# SmartRock_EC.net
KiCad netlist of a schematic drawn in EAGLE
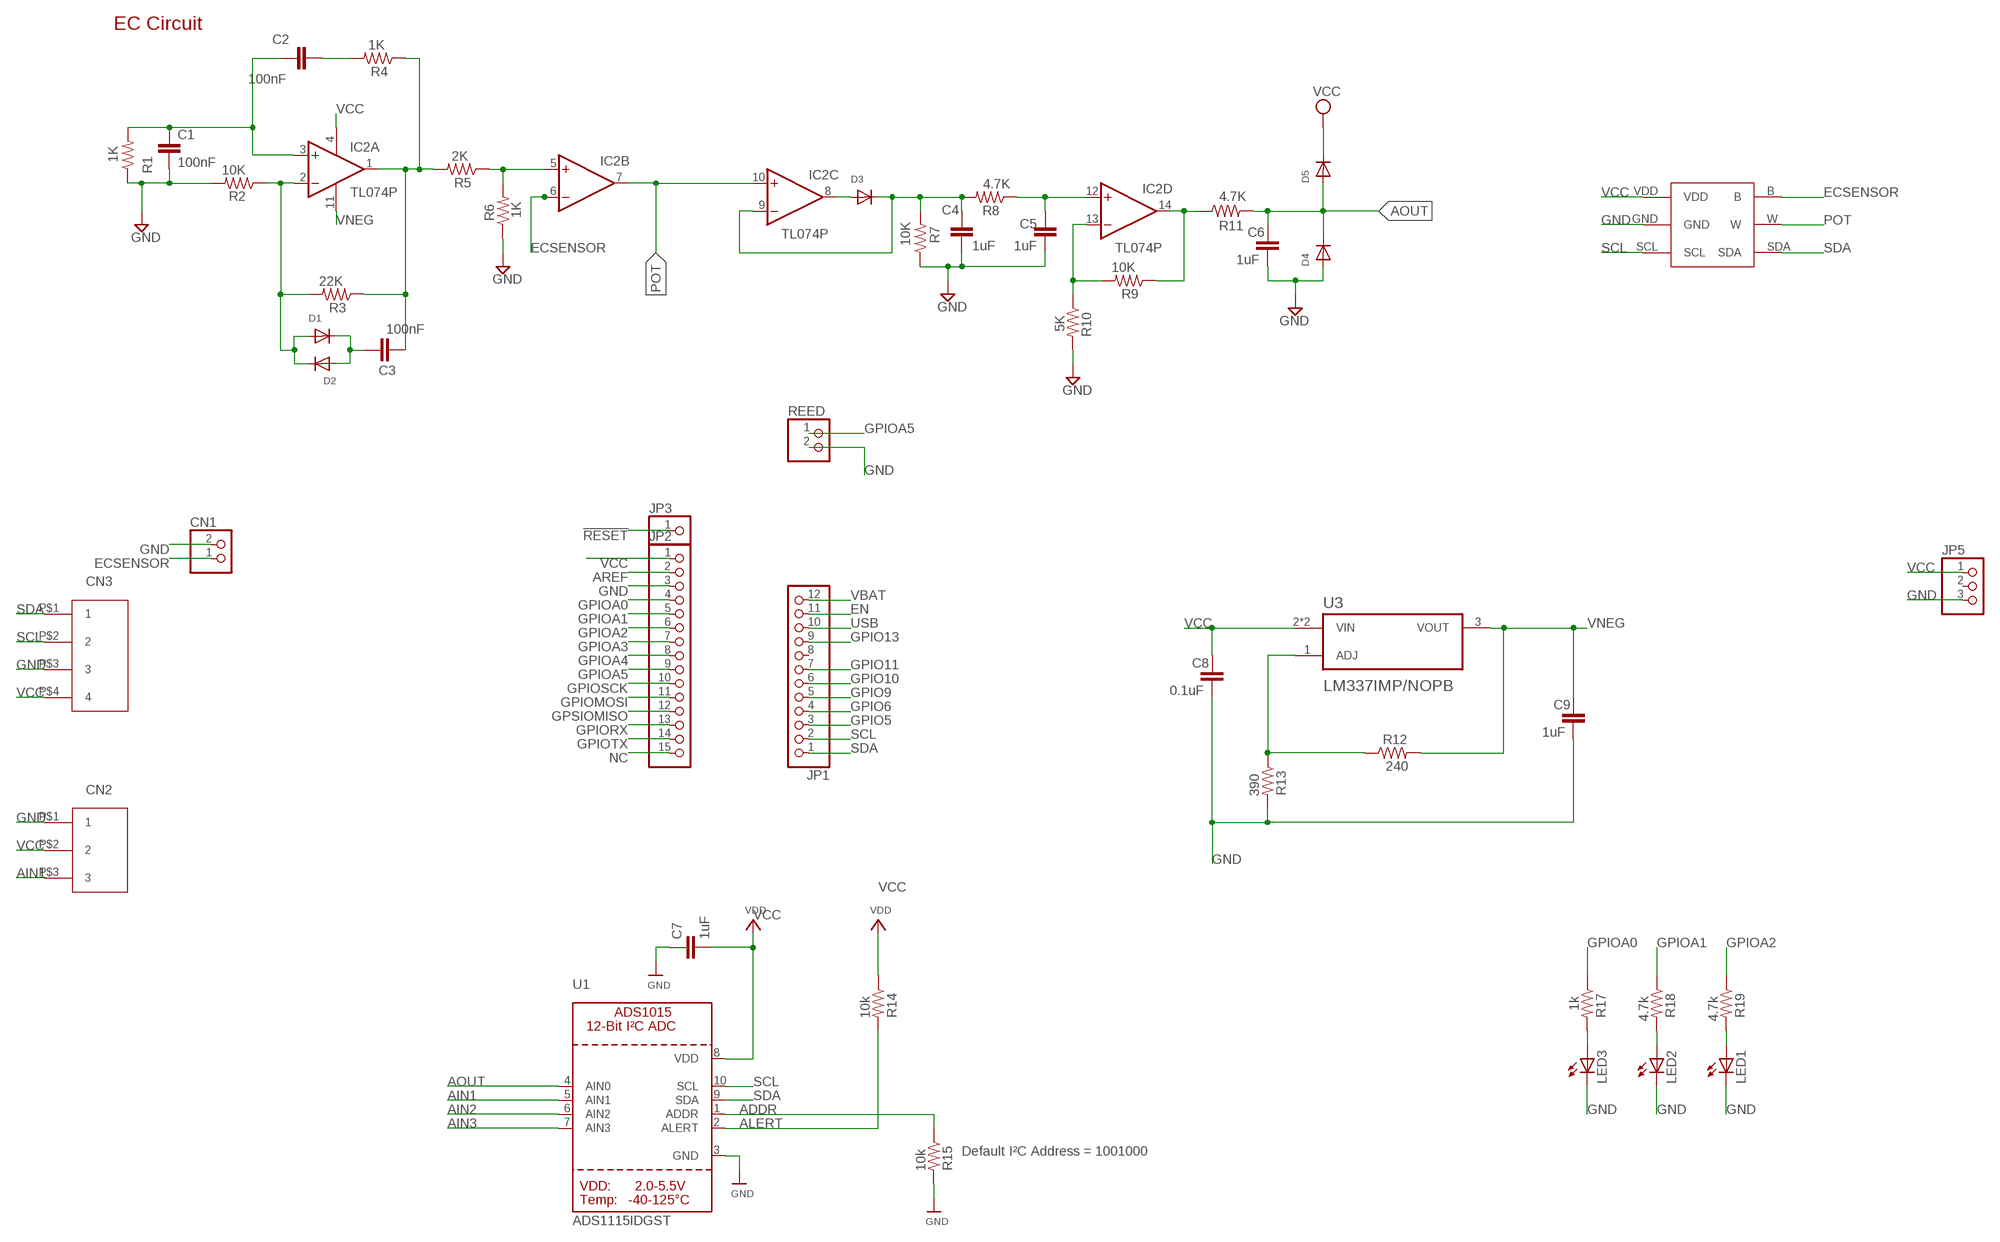
[diagram p0: schematic, sheet 1]

(export (version "E")
  (design (tool "Eeschema 10.0.6"))
  (components
    (comp (ref "C1")
      (value "100nF")
      (footprint "eagle-import:C1206")
      (libsource (lib "eagle-import") (part "C-EUC1206"))
    )
    (comp (ref "C2")
      (value "100nF")
      (footprint "eagle-import:C1206")
      (libsource (lib "eagle-import") (part "C-EUC1206"))
    )
    (comp (ref "C3")
      (value "100nF")
      (footprint "eagle-import:C1206")
      (libsource (lib "eagle-import") (part "C-EUC1206"))
    )
    (comp (ref "C4")
      (value "1uF")
      (footprint "eagle-import:C1206")
      (libsource (lib "eagle-import") (part "C-EUC1206"))
    )
    (comp (ref "C5")
      (value "1uF")
      (footprint "eagle-import:C1206")
      (libsource (lib "eagle-import") (part "C-EUC1206"))
    )
    (comp (ref "C6")
      (value "1uF")
      (footprint "eagle-import:C1206")
      (libsource (lib "eagle-import") (part "C-EUC1206"))
    )
    (comp (ref "C7")
      (value "1uF")
      (footprint "eagle-import:C1206")
      (libsource (lib "eagle-import") (part "C-EUC1206"))
    )
    (comp (ref "C8")
      (value "0.1uF")
      (footprint "eagle-import:C1206")
      (libsource (lib "eagle-import") (part "C-EUC1206"))
    )
    (comp (ref "C9")
      (value "1uF")
      (footprint "eagle-import:C1206")
      (libsource (lib "eagle-import") (part "C-EUC1206"))
    )
    (comp (ref "CN1")
      (value "JST_2PIN-THM")
      (footprint "eagle-import:JST-PH-2-THM")
      (libsource (lib "eagle-import") (part "JST_2PIN-THM"))
    )
    (comp (ref "D1")
      (value "DIODEDO-1N4148")
      (footprint "eagle-import:DO-1N4148")
      (libsource (lib "eagle-import") (part "DIODEDO-1N4148"))
    )
    (comp (ref "D2")
      (value "DIODEDO-1N4148")
      (footprint "eagle-import:DO-1N4148")
      (libsource (lib "eagle-import") (part "DIODEDO-1N4148"))
    )
    (comp (ref "D3")
      (value "DIODEDO-1N4148")
      (footprint "eagle-import:DO-1N4148")
      (libsource (lib "eagle-import") (part "DIODEDO-1N4148"))
    )
    (comp (ref "D4")
      (value "DIODEDO-1N4148")
      (footprint "eagle-import:DO-1N4148")
      (libsource (lib "eagle-import") (part "DIODEDO-1N4148"))
    )
    (comp (ref "D5")
      (value "DIODEDO-1N4148")
      (footprint "eagle-import:DO-1N4148")
      (libsource (lib "eagle-import") (part "DIODEDO-1N4148"))
    )
    (comp (ref "IC2")
      (value "TL074P")
      (footprint "eagle-import:DIL14")
      (libsource (lib "eagle-import") (part "TL074P"))
    )
    (comp (ref "JP1")
      (value "PINHD-1X12-CB")
      (footprint "eagle-import:1X12-CB")
      (libsource (lib "eagle-import") (part "PINHD-1X12-CB"))
    )
    (comp (ref "JP2")
      (value "PINHD-1X15-CB")
      (footprint "eagle-import:1X15-CB")
      (libsource (lib "eagle-import") (part "PINHD-1X15-CB"))
    )
    (comp (ref "JP3")
      (value "PINHD-1X1CB")
      (footprint "eagle-import:1X01-CLEANBIG")
      (libsource (lib "eagle-import") (part "PINHD-1X1CB"))
    )
    (comp (ref "JP5")
      (value "PINHD-1X3CB")
      (footprint "eagle-import:1X03-CLEANBIG")
      (libsource (lib "eagle-import") (part "PINHD-1X3CB"))
    )
    (comp (ref "LED1")
      (value "LEDSMT1206")
      (footprint "eagle-import:1206")
      (libsource (lib "eagle-import") (part "LEDSMT1206"))
    )
    (comp (ref "LED2")
      (value "LEDSMT1206")
      (footprint "eagle-import:1206")
      (libsource (lib "eagle-import") (part "LEDSMT1206"))
    )
    (comp (ref "LED3")
      (value "LEDSMT1206")
      (footprint "eagle-import:1206")
      (libsource (lib "eagle-import") (part "LEDSMT1206"))
    )
    (comp (ref "R1")
      (value "1K")
      (footprint "eagle-import:R1206")
      (libsource (lib "eagle-import") (part "R-US_R1206"))
    )
    (comp (ref "R2")
      (value "10K")
      (footprint "eagle-import:R1206")
      (libsource (lib "eagle-import") (part "R-US_R1206"))
    )
    (comp (ref "R3")
      (value "22K")
      (footprint "eagle-import:R1206")
      (libsource (lib "eagle-import") (part "R-US_R1206"))
    )
    (comp (ref "R4")
      (value "1K")
      (footprint "eagle-import:R1206")
      (libsource (lib "eagle-import") (part "R-US_R1206"))
    )
    (comp (ref "R5")
      (value "2K")
      (footprint "eagle-import:R1206")
      (libsource (lib "eagle-import") (part "R-US_R1206"))
    )
    (comp (ref "R6")
      (value "1K")
      (footprint "eagle-import:R1206")
      (libsource (lib "eagle-import") (part "R-US_R1206"))
    )
    (comp (ref "R7")
      (value "10K")
      (footprint "eagle-import:R1206")
      (libsource (lib "eagle-import") (part "R-US_R1206"))
    )
    (comp (ref "R8")
      (value "4.7K")
      (footprint "eagle-import:R1206")
      (libsource (lib "eagle-import") (part "R-US_R1206"))
    )
    (comp (ref "R9")
      (value "10K")
      (footprint "eagle-import:R1206")
      (libsource (lib "eagle-import") (part "R-US_R1206"))
    )
    (comp (ref "R10")
      (value "5K")
      (footprint "eagle-import:R1206")
      (libsource (lib "eagle-import") (part "R-US_R1206"))
    )
    (comp (ref "R11")
      (value "4.7K")
      (footprint "eagle-import:R1206")
      (libsource (lib "eagle-import") (part "R-US_R1206"))
    )
    (comp (ref "R12")
      (value "240")
      (footprint "eagle-import:R1206")
      (libsource (lib "eagle-import") (part "R-US_R1206"))
    )
    (comp (ref "R13")
      (value "390")
      (footprint "eagle-import:R1206")
      (libsource (lib "eagle-import") (part "R-US_R1206"))
    )
    (comp (ref "R14")
      (value "10k")
      (footprint "eagle-import:R1206")
      (libsource (lib "eagle-import") (part "R-US_R1206"))
    )
    (comp (ref "R15")
      (value "10k")
      (footprint "eagle-import:R1206")
      (libsource (lib "eagle-import") (part "R-US_R1206"))
    )
    (comp (ref "R17")
      (value "1k")
      (footprint "eagle-import:R1206")
      (libsource (lib "eagle-import") (part "R-US_R1206"))
    )
    (comp (ref "R18")
      (value "4.7k")
      (footprint "eagle-import:R1206")
      (libsource (lib "eagle-import") (part "R-US_R1206"))
    )
    (comp (ref "R19")
      (value "4.7k")
      (footprint "eagle-import:R1206")
      (libsource (lib "eagle-import") (part "R-US_R1206"))
    )
    (comp (ref "REED")
      (value "PINHD-1X2")
      (footprint "eagle-import:1X02")
      (libsource (lib "eagle-import") (part "PINHD-1X2"))
    )
    (comp (ref "U$1")
      (value "AD5246")
      (footprint "eagle-import:AD5246")
      (libsource (lib "eagle-import") (part "AD5246"))
    )
    (comp (ref "U$7")
      (value "JST_4PIN_2MM")
      (footprint "eagle-import:JST_4PIN_2MM")
      (libsource (lib "eagle-import") (part "JST_4PIN_2MM"))
    )
    (comp (ref "U$9")
      (value "JST_3PIN_2MM")
      (footprint "eagle-import:JST_3PIN_2MM")
      (libsource (lib "eagle-import") (part "JST_3PIN_2MM"))
    )
    (comp (ref "U1")
      (value "ADS1115IDGST")
      (footprint "eagle-import:MSOP10")
      (libsource (lib "eagle-import") (part "ADC_ADS1015"))
    )
    (comp (ref "U3")
      (value "LM337IMP/NOPB")
      (footprint "eagle-import:SOT230P700X180-4N")
      (fields
        (field (name "DIGI-KEY_PART_NUMBER") "LM337IMPCT-ND")
        (field (name "MF") "Texas Instruments")
        (field (name "MP") "LM337IMP")
      )
      (libsource (lib "eagle-import") (part "LM337IMP/NOPB"))
    )
  )
  (nets
    (net (code "1") (name "/ADDR") (class "Default")
      (node (ref "R15") (pin "1") (pinfunction "1_1") (pintype "passive"))
      (node (ref "U1") (pin "1") (pinfunction "ADDR_1") (pintype "bidirectional"))
    )
    (net (code "2") (name "/AIN1") (class "Default")
      (node (ref "U$9") (pin "P$3") (pinfunction "3_P$3") (pintype "bidirectional"))
      (node (ref "U1") (pin "5") (pinfunction "AIN1_5") (pintype "bidirectional"))
    )
    (net (code "3") (name "/AIN2") (class "Default")
      (node (ref "U1") (pin "6") (pinfunction "AIN2_6") (pintype "bidirectional"))
    )
    (net (code "4") (name "/AIN3") (class "Default")
      (node (ref "U1") (pin "7") (pinfunction "AIN3_7") (pintype "bidirectional"))
    )
    (net (code "5") (name "/ALERT") (class "Default")
      (node (ref "R14") (pin "2") (pinfunction "2_2") (pintype "passive"))
      (node (ref "U1") (pin "2") (pinfunction "ALERT_2") (pintype "bidirectional"))
    )
    (net (code "6") (name "/AREF") (class "Default")
      (node (ref "JP2") (pin "2") (pinfunction "2_2") (pintype "passive"))
    )
    (net (code "7") (name "/ECSENSOR") (class "Default")
      (node (ref "CN1") (pin "1") (pinfunction "2_1") (pintype "passive"))
      (node (ref "IC2") (pin "6") (pinfunction "-IN_6") (pintype "input"))
      (node (ref "U$1") (pin "B") (pinfunction "B_B") (pintype "bidirectional"))
    )
    (net (code "8") (name "/EN") (class "Default")
      (node (ref "JP1") (pin "11") (pinfunction "11_11") (pintype "passive"))
    )
    (net (code "9") (name "/GPIO5") (class "Default")
      (node (ref "JP1") (pin "3") (pinfunction "3_3") (pintype "passive"))
    )
    (net (code "10") (name "/GPIO6") (class "Default")
      (node (ref "JP1") (pin "4") (pinfunction "4_4") (pintype "passive"))
    )
    (net (code "11") (name "/GPIO9") (class "Default")
      (node (ref "JP1") (pin "5") (pinfunction "5_5") (pintype "passive"))
    )
    (net (code "12") (name "/GPIO10") (class "Default")
      (node (ref "JP1") (pin "6") (pinfunction "6_6") (pintype "passive"))
    )
    (net (code "13") (name "/GPIO11") (class "Default")
      (node (ref "JP1") (pin "7") (pinfunction "7_7") (pintype "passive"))
    )
    (net (code "14") (name "/GPIO13") (class "Default")
      (node (ref "JP1") (pin "9") (pinfunction "9_9") (pintype "passive"))
    )
    (net (code "15") (name "/GPIOA0") (class "Default")
      (node (ref "JP2") (pin "4") (pinfunction "4_4") (pintype "passive"))
      (node (ref "R17") (pin "1") (pinfunction "1_1") (pintype "passive"))
    )
    (net (code "16") (name "/GPIOA1") (class "Default")
      (node (ref "JP2") (pin "5") (pinfunction "5_5") (pintype "passive"))
      (node (ref "R18") (pin "1") (pinfunction "1_1") (pintype "passive"))
    )
    (net (code "17") (name "/GPIOA2") (class "Default")
      (node (ref "JP2") (pin "6") (pinfunction "6_6") (pintype "passive"))
      (node (ref "R19") (pin "1") (pinfunction "1_1") (pintype "passive"))
    )
    (net (code "18") (name "/GPIOA3") (class "Default")
      (node (ref "JP2") (pin "7") (pinfunction "7_7") (pintype "passive"))
    )
    (net (code "19") (name "/GPIOA4") (class "Default")
      (node (ref "JP2") (pin "8") (pinfunction "8_8") (pintype "passive"))
    )
    (net (code "20") (name "/GPIOA5") (class "Default")
      (node (ref "JP2") (pin "9") (pinfunction "9_9") (pintype "passive"))
      (node (ref "REED") (pin "1") (pinfunction "1_1") (pintype "passive"))
    )
    (net (code "21") (name "/GPIOMOSI") (class "Default")
      (node (ref "JP2") (pin "11") (pinfunction "11_11") (pintype "passive"))
    )
    (net (code "22") (name "/GPIORX") (class "Default")
      (node (ref "JP2") (pin "13") (pinfunction "13_13") (pintype "passive"))
    )
    (net (code "23") (name "/GPIOSCK") (class "Default")
      (node (ref "JP2") (pin "10") (pinfunction "10_10") (pintype "passive"))
    )
    (net (code "24") (name "/GPIOTX") (class "Default")
      (node (ref "JP2") (pin "14") (pinfunction "14_14") (pintype "passive"))
    )
    (net (code "25") (name "/GPSIOMISO") (class "Default")
      (node (ref "JP2") (pin "12") (pinfunction "12_12") (pintype "passive"))
    )
    (net (code "26") (name "/NC") (class "Default")
      (node (ref "JP2") (pin "15") (pinfunction "15_15") (pintype "passive"))
    )
    (net (code "27") (name "/SCL") (class "Default")
      (node (ref "JP1") (pin "2") (pinfunction "2_2") (pintype "passive"))
      (node (ref "U$1") (pin "SCL") (pinfunction "SCL_SCL") (pintype "bidirectional"))
      (node (ref "U$7") (pin "P$2") (pinfunction "2_P$2") (pintype "bidirectional"))
      (node (ref "U1") (pin "10") (pinfunction "SCL_10") (pintype "bidirectional"))
    )
    (net (code "28") (name "/SDA") (class "Default")
      (node (ref "JP1") (pin "1") (pinfunction "1_1") (pintype "passive"))
      (node (ref "U$1") (pin "SDA") (pinfunction "SDA_SDA") (pintype "bidirectional"))
      (node (ref "U$7") (pin "P$1") (pinfunction "1_P$1") (pintype "bidirectional"))
      (node (ref "U1") (pin "9") (pinfunction "SDA_9") (pintype "bidirectional"))
    )
    (net (code "29") (name "/USB") (class "Default")
      (node (ref "JP1") (pin "10") (pinfunction "10_10") (pintype "passive"))
    )
    (net (code "30") (name "/VBAT") (class "Default")
      (node (ref "JP1") (pin "12") (pinfunction "12_12") (pintype "passive"))
    )
    (net (code "31") (name "/VNEG") (class "Default")
      (node (ref "C9") (pin "2") (pinfunction "2_2") (pintype "passive"))
      (node (ref "IC2") (pin "11") (pinfunction "V-_11") (pintype "power_in"))
      (node (ref "R12") (pin "2") (pinfunction "2_2") (pintype "passive"))
      (node (ref "U3") (pin "3") (pinfunction "VOUT_3") (pintype "output"))
    )
    (net (code "32") (name "/~{RESET}") (class "Default")
      (node (ref "JP3") (pin "1") (pinfunction "1_1") (pintype "passive"))
    )
    (net (code "33") (name "AOUT") (class "Default")
      (node (ref "C6") (pin "2") (pinfunction "2_2") (pintype "passive"))
      (node (ref "D4") (pin "C") (pinfunction "C_C") (pintype "passive"))
      (node (ref "D5") (pin "A") (pinfunction "A_A") (pintype "passive"))
      (node (ref "R11") (pin "2") (pinfunction "2_2") (pintype "passive"))
      (node (ref "U1") (pin "4") (pinfunction "AIN0_4") (pintype "bidirectional"))
    )
    (net (code "34") (name "GND") (class "Default")
      (node (ref "C1") (pin "2") (pinfunction "2_2") (pintype "passive"))
      (node (ref "C4") (pin "1") (pinfunction "1_1") (pintype "passive"))
      (node (ref "C5") (pin "1") (pinfunction "1_1") (pintype "passive"))
      (node (ref "C6") (pin "1") (pinfunction "1_1") (pintype "passive"))
      (node (ref "C7") (pin "1") (pinfunction "1_1") (pintype "passive"))
      (node (ref "C8") (pin "1") (pinfunction "1_1") (pintype "passive"))
      (node (ref "C9") (pin "1") (pinfunction "1_1") (pintype "passive"))
      (node (ref "CN1") (pin "2") (pinfunction "1_2") (pintype "passive"))
      (node (ref "D4") (pin "A") (pinfunction "A_A") (pintype "passive"))
      (node (ref "JP2") (pin "3") (pinfunction "3_3") (pintype "passive"))
      (node (ref "JP5") (pin "3") (pinfunction "3_3") (pintype "passive"))
      (node (ref "LED1") (pin "C") (pinfunction "C_C") (pintype "passive"))
      (node (ref "LED2") (pin "C") (pinfunction "C_C") (pintype "passive"))
      (node (ref "LED3") (pin "C") (pinfunction "C_C") (pintype "passive"))
      (node (ref "R1") (pin "1") (pinfunction "1_1") (pintype "passive"))
      (node (ref "R10") (pin "2") (pinfunction "2_2") (pintype "passive"))
      (node (ref "R13") (pin "2") (pinfunction "2_2") (pintype "passive"))
      (node (ref "R15") (pin "2") (pinfunction "2_2") (pintype "passive"))
      (node (ref "R2") (pin "2") (pinfunction "2_2") (pintype "passive"))
      (node (ref "R6") (pin "1") (pinfunction "1_1") (pintype "passive"))
      (node (ref "R7") (pin "1") (pinfunction "1_1") (pintype "passive"))
      (node (ref "REED") (pin "2") (pinfunction "2_2") (pintype "passive"))
      (node (ref "U$1") (pin "GND") (pinfunction "GND_GND") (pintype "bidirectional"))
      (node (ref "U$7") (pin "P$3") (pinfunction "3_P$3") (pintype "bidirectional"))
      (node (ref "U$9") (pin "P$1") (pinfunction "1_P$1") (pintype "bidirectional"))
      (node (ref "U1") (pin "3") (pinfunction "GND_3") (pintype "bidirectional"))
    )
    (net (code "35") (name "Net-(C2-Pad2)") (class "Default")
      (node (ref "C2") (pin "2") (pinfunction "2_2") (pintype "passive"))
      (node (ref "R4") (pin "2") (pinfunction "2_2") (pintype "passive"))
    )
    (net (code "36") (name "Net-(C3-Pad1)") (class "Default")
      (node (ref "C3") (pin "1") (pinfunction "1_1") (pintype "passive"))
      (node (ref "D1") (pin "C") (pinfunction "C_C") (pintype "passive"))
      (node (ref "D2") (pin "A") (pinfunction "A_A") (pintype "passive"))
    )
    (net (code "37") (name "Net-(IC2A-+IN)") (class "Default")
      (node (ref "C1") (pin "1") (pinfunction "1_1") (pintype "passive"))
      (node (ref "C2") (pin "1") (pinfunction "1_1") (pintype "passive"))
      (node (ref "IC2") (pin "3") (pinfunction "+IN_3") (pintype "input"))
      (node (ref "R1") (pin "2") (pinfunction "2_2") (pintype "passive"))
    )
    (net (code "38") (name "Net-(IC2A--IN)") (class "Default")
      (node (ref "D1") (pin "A") (pinfunction "A_A") (pintype "passive"))
      (node (ref "D2") (pin "C") (pinfunction "C_C") (pintype "passive"))
      (node (ref "IC2") (pin "2") (pinfunction "-IN_2") (pintype "input"))
      (node (ref "R2") (pin "1") (pinfunction "1_1") (pintype "passive"))
      (node (ref "R3") (pin "2") (pinfunction "2_2") (pintype "passive"))
    )
    (net (code "39") (name "Net-(IC2A-OUT)") (class "Default")
      (node (ref "C3") (pin "2") (pinfunction "2_2") (pintype "passive"))
      (node (ref "IC2") (pin "1") (pinfunction "OUT_1") (pintype "output"))
      (node (ref "R3") (pin "1") (pinfunction "1_1") (pintype "passive"))
      (node (ref "R4") (pin "1") (pinfunction "1_1") (pintype "passive"))
      (node (ref "R5") (pin "2") (pinfunction "2_2") (pintype "passive"))
    )
    (net (code "40") (name "Net-(IC2B-+IN)") (class "Default")
      (node (ref "IC2") (pin "5") (pinfunction "+IN_5") (pintype "input"))
      (node (ref "R5") (pin "1") (pinfunction "1_1") (pintype "passive"))
      (node (ref "R6") (pin "2") (pinfunction "2_2") (pintype "passive"))
    )
    (net (code "41") (name "Net-(IC2C--IN)") (class "Default")
      (node (ref "C4") (pin "2") (pinfunction "2_2") (pintype "passive"))
      (node (ref "D3") (pin "C") (pinfunction "C_C") (pintype "passive"))
      (node (ref "IC2") (pin "9") (pinfunction "-IN_9") (pintype "input"))
      (node (ref "R7") (pin "2") (pinfunction "2_2") (pintype "passive"))
      (node (ref "R8") (pin "2") (pinfunction "2_2") (pintype "passive"))
    )
    (net (code "42") (name "Net-(IC2C-OUT)") (class "Default")
      (node (ref "D3") (pin "A") (pinfunction "A_A") (pintype "passive"))
      (node (ref "IC2") (pin "8") (pinfunction "OUT_8") (pintype "output"))
    )
    (net (code "43") (name "Net-(IC2D-+IN)") (class "Default")
      (node (ref "C5") (pin "2") (pinfunction "2_2") (pintype "passive"))
      (node (ref "IC2") (pin "12") (pinfunction "+IN_12") (pintype "input"))
      (node (ref "R8") (pin "1") (pinfunction "1_1") (pintype "passive"))
    )
    (net (code "44") (name "Net-(IC2D--IN)") (class "Default")
      (node (ref "IC2") (pin "13") (pinfunction "-IN_13") (pintype "input"))
      (node (ref "R10") (pin "1") (pinfunction "1_1") (pintype "passive"))
      (node (ref "R9") (pin "2") (pinfunction "2_2") (pintype "passive"))
    )
    (net (code "45") (name "Net-(IC2D-OUT)") (class "Default")
      (node (ref "IC2") (pin "14") (pinfunction "OUT_14") (pintype "output"))
      (node (ref "R11") (pin "1") (pinfunction "1_1") (pintype "passive"))
      (node (ref "R9") (pin "1") (pinfunction "1_1") (pintype "passive"))
    )
    (net (code "46") (name "Net-(LED1-PadA)") (class "Default")
      (node (ref "LED1") (pin "A") (pinfunction "A_A") (pintype "passive"))
      (node (ref "R19") (pin "2") (pinfunction "2_2") (pintype "passive"))
    )
    (net (code "47") (name "Net-(LED2-PadA)") (class "Default")
      (node (ref "LED2") (pin "A") (pinfunction "A_A") (pintype "passive"))
      (node (ref "R18") (pin "2") (pinfunction "2_2") (pintype "passive"))
    )
    (net (code "48") (name "Net-(LED3-PadA)") (class "Default")
      (node (ref "LED3") (pin "A") (pinfunction "A_A") (pintype "passive"))
      (node (ref "R17") (pin "2") (pinfunction "2_2") (pintype "passive"))
    )
    (net (code "49") (name "Net-(U3-ADJ)") (class "Default")
      (node (ref "R12") (pin "1") (pinfunction "1_1") (pintype "passive"))
      (node (ref "R13") (pin "1") (pinfunction "1_1") (pintype "passive"))
      (node (ref "U3") (pin "1") (pinfunction "ADJ_1") (pintype "bidirectional"))
    )
    (net (code "50") (name "POT") (class "Default")
      (node (ref "IC2") (pin "10") (pinfunction "+IN_10") (pintype "input"))
      (node (ref "IC2") (pin "7") (pinfunction "OUT_7") (pintype "output"))
      (node (ref "U$1") (pin "W") (pinfunction "W_W") (pintype "bidirectional"))
    )
    (net (code "51") (name "VCC") (class "Default")
      (node (ref "C7") (pin "2") (pinfunction "2_2") (pintype "passive"))
      (node (ref "C8") (pin "2") (pinfunction "2_2") (pintype "passive"))
      (node (ref "D5") (pin "C") (pinfunction "C_C") (pintype "passive"))
      (node (ref "IC2") (pin "4") (pinfunction "V+_4") (pintype "power_in"))
      (node (ref "JP2") (pin "1") (pinfunction "1_1") (pintype "passive"))
      (node (ref "JP5") (pin "1") (pinfunction "1_1") (pintype "passive"))
      (node (ref "R14") (pin "1") (pinfunction "1_1") (pintype "passive"))
      (node (ref "U$1") (pin "VDD") (pinfunction "VDD_VDD") (pintype "bidirectional"))
      (node (ref "U$7") (pin "P$4") (pinfunction "4_P$4") (pintype "bidirectional"))
      (node (ref "U$9") (pin "P$2") (pinfunction "2_P$2") (pintype "bidirectional"))
      (node (ref "U1") (pin "8") (pinfunction "VDD_8") (pintype "bidirectional"))
      (node (ref "U3") (pin "2") (pinfunction "VIN_2") (pintype "input"))
      (node (ref "U3") (pin "4") (pinfunction "VIN_4") (pintype "input"))
    )
    (net (code "52") (name "unconnected-(JP1-Pad8)") (class "Default")
      (node (ref "JP1") (pin "8") (pinfunction "8_8") (pintype "passive"))
    )
    (net (code "53") (name "unconnected-(JP5-Pad2)") (class "Default")
      (node (ref "JP5") (pin "2") (pinfunction "2_2") (pintype "passive"))
    )
  )
)
